# i2-mb_rpi_s.net
KiCad netlist of a schematic drawn in EAGLE
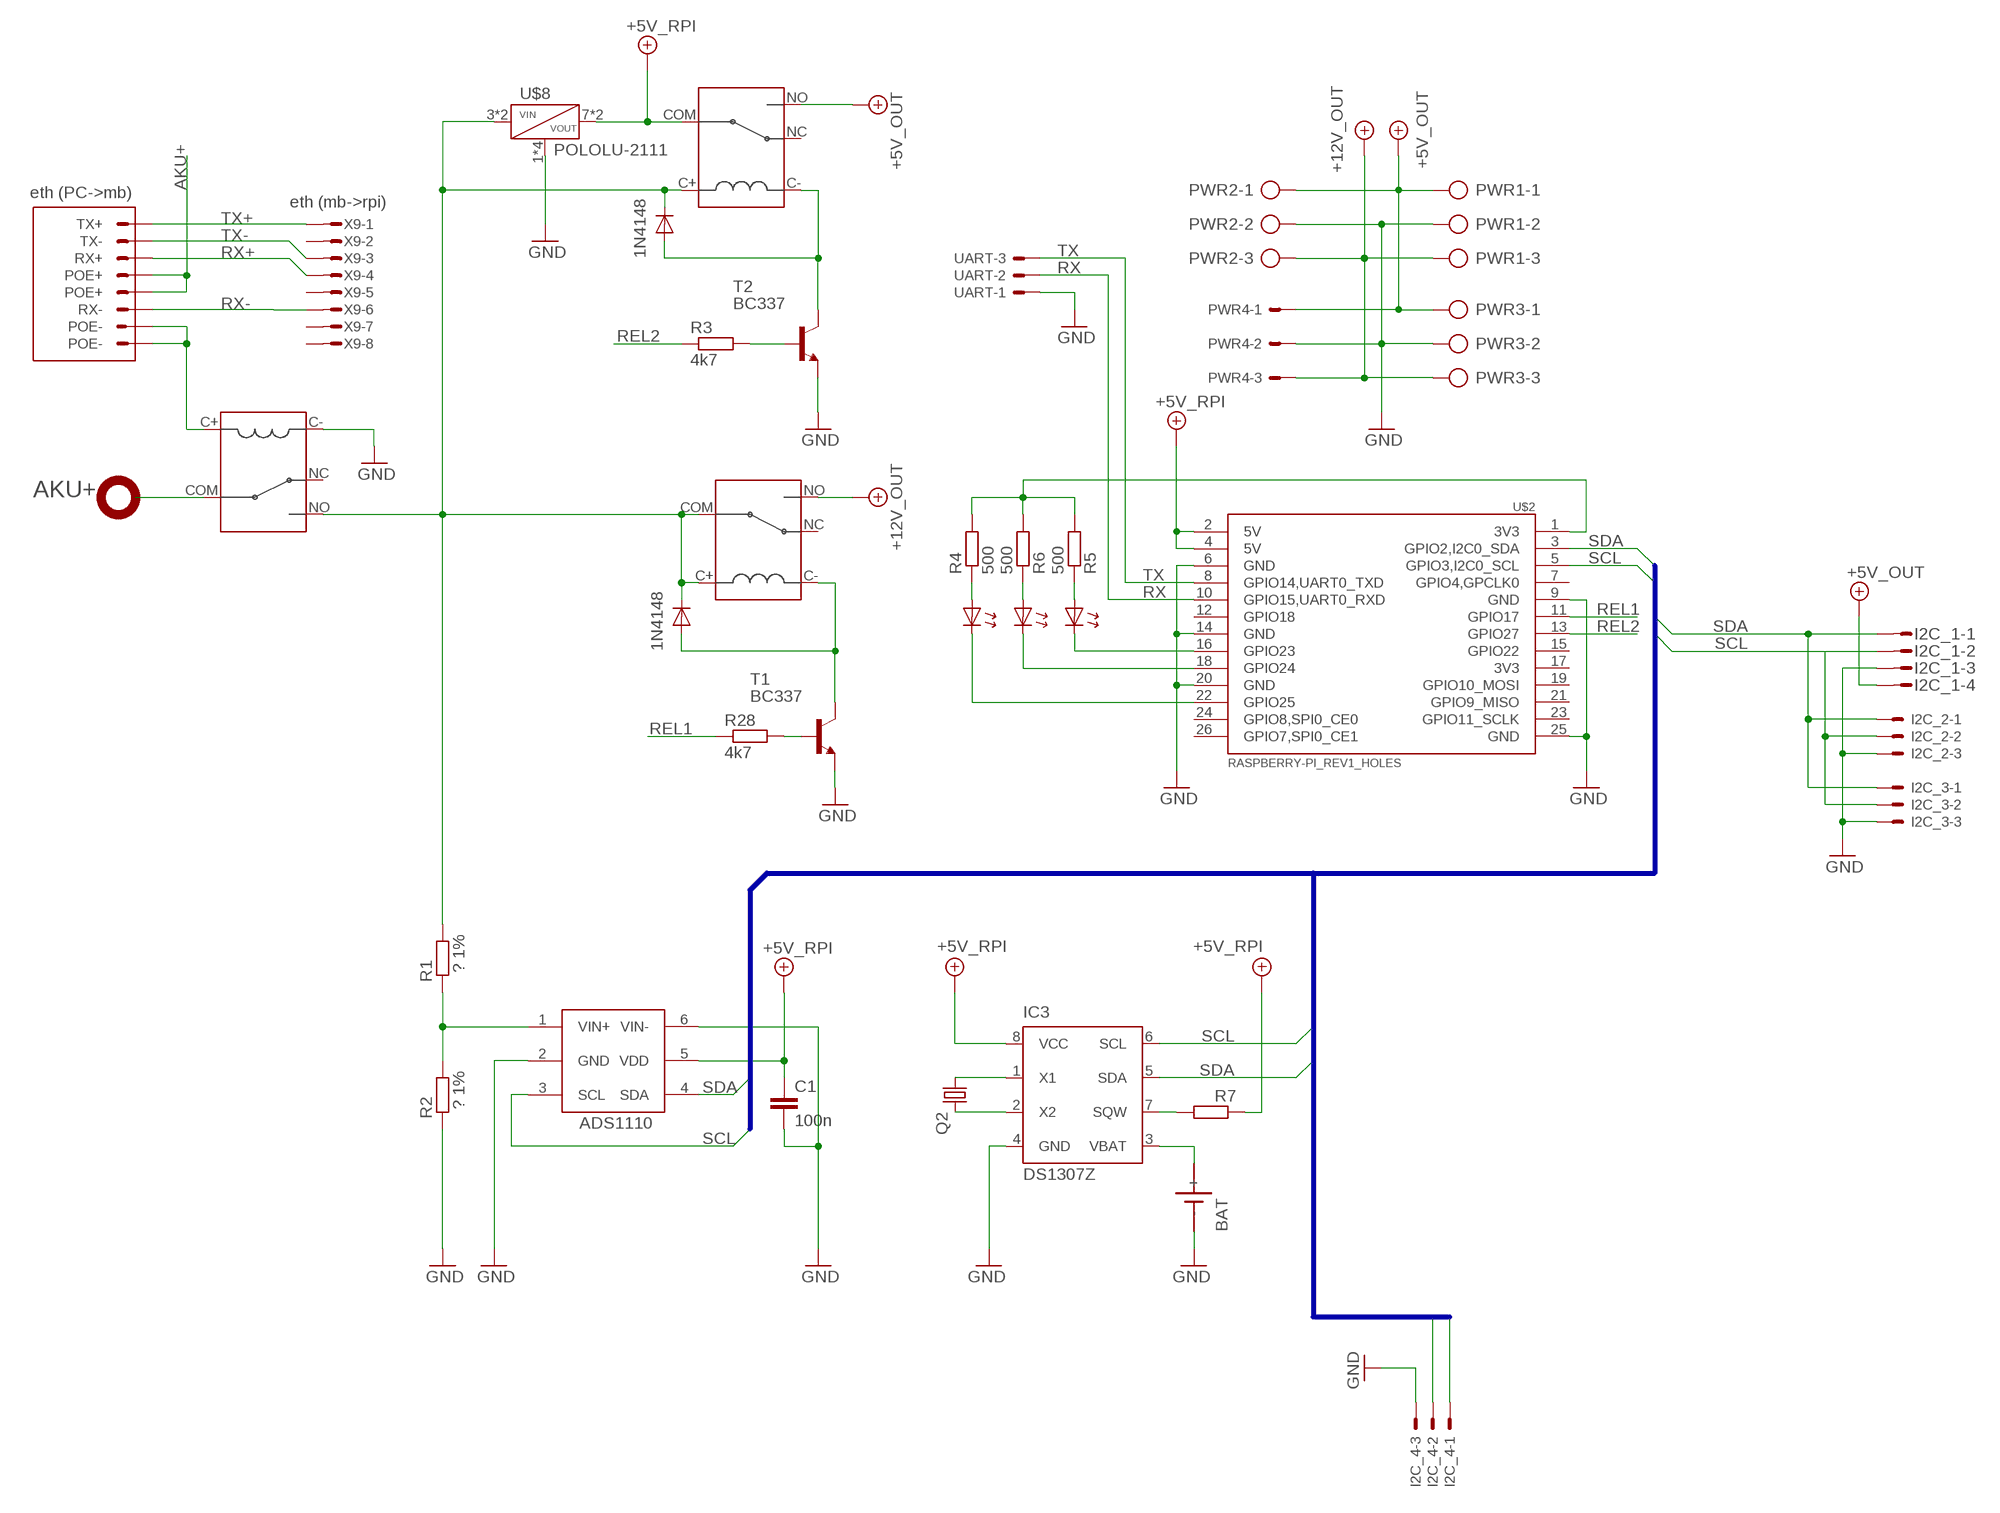
[diagram p0: schematic, sheet 1]

(export (version "E")
  (design (tool "Eeschema 10.0.6"))
  (components
    (comp (ref "BAT")
      (value "SN2032")
      (footprint "eagle-import:SN2032")
      (libsource (lib "eagle-import") (part "SN2032"))
    )
    (comp (ref "C1")
      (value "100n")
      (footprint "eagle-import:C0603")
      (libsource (lib "eagle-import") (part "C-EUC0603"))
    )
    (comp (ref "I2C_1")
      (value "MICROMATCH-4")
      (footprint "eagle-import:MICROMATCH-4")
      (fields (field (name "MPN") "7-215464-4"))
      (libsource (lib "eagle-import") (part "MICROMATCH-4"))
    )
    (comp (ref "I2C_2")
      (value "C-GRID-03-70553")
      (footprint "eagle-import:70553-03")
      (libsource (lib "eagle-import") (part "C-GRID-03-70553"))
    )
    (comp (ref "I2C_3")
      (value "C-GRID-03-70553")
      (footprint "eagle-import:70553-03")
      (libsource (lib "eagle-import") (part "C-GRID-03-70553"))
    )
    (comp (ref "I2C_4")
      (value "C-GRID-03-70553")
      (footprint "eagle-import:70553-03")
      (libsource (lib "eagle-import") (part "C-GRID-03-70553"))
    )
    (comp (ref "IC1")
      (value "ADS1110")
      (footprint "eagle-import:SOT-23-6")
      (libsource (lib "eagle-import") (part "ADS1110"))
    )
    (comp (ref "IC3")
      (value "DS1307Z")
      (footprint "eagle-import:SOIC8")
      (libsource (lib "eagle-import") (part "DS1307Z"))
    )
    (comp (ref "LED1")
      (value "LED0603")
      (footprint "eagle-import:D0603")
      (libsource (lib "eagle-import") (part "LED0603"))
    )
    (comp (ref "LED2")
      (value "LED0603")
      (footprint "eagle-import:D0603")
      (libsource (lib "eagle-import") (part "LED0603"))
    )
    (comp (ref "LED3")
      (value "LED0603")
      (footprint "eagle-import:D0603")
      (libsource (lib "eagle-import") (part "LED0603"))
    )
    (comp (ref "PWR1")
      (value "TBMP5103RC-KFV1")
      (footprint "eagle-import:TBMP5103RC-KF")
      (libsource (lib "eagle-import") (part "TBMP5103RC-KFV1"))
    )
    (comp (ref "PWR2")
      (value "TBMP5103RC-KFV1")
      (footprint "eagle-import:TBMP5103RC-KF")
      (libsource (lib "eagle-import") (part "TBMP5103RC-KFV1"))
    )
    (comp (ref "PWR3")
      (value "TBMP5103RC-KFV1")
      (footprint "eagle-import:TBMP5103RC-KF")
      (libsource (lib "eagle-import") (part "TBMP5103RC-KFV1"))
    )
    (comp (ref "PWR4")
      (value "C-GRID-03-70543")
      (footprint "eagle-import:70543-03")
      (libsource (lib "eagle-import") (part "C-GRID-03-70543"))
    )
    (comp (ref "Q2")
      (value "CRYSTAL")
      (footprint "eagle-import:CFPX-217")
      (libsource (lib "eagle-import") (part "CRYSTAL"))
    )
    (comp (ref "R1")
      (value "? 1%")
      (footprint "eagle-import:R0603")
      (libsource (lib "eagle-import") (part "R-EU_R0603"))
    )
    (comp (ref "R2")
      (value "? 1%")
      (footprint "eagle-import:R0603")
      (libsource (lib "eagle-import") (part "R-EU_R0603"))
    )
    (comp (ref "R3")
      (value "4k7")
      (footprint "eagle-import:R0603")
      (libsource (lib "eagle-import") (part "R-EU_R0603"))
    )
    (comp (ref "R4")
      (value "500")
      (footprint "eagle-import:R0603")
      (libsource (lib "eagle-import") (part "R-EU_R0603"))
    )
    (comp (ref "R5")
      (value "500")
      (footprint "eagle-import:R0603")
      (libsource (lib "eagle-import") (part "R-EU_R0603"))
    )
    (comp (ref "R6")
      (value "500")
      (footprint "eagle-import:R0603")
      (libsource (lib "eagle-import") (part "R-EU_R0603"))
    )
    (comp (ref "R7")
      (value "R-EU_R0603")
      (footprint "eagle-import:R0603")
      (libsource (lib "eagle-import") (part "R-EU_R0603"))
    )
    (comp (ref "R28")
      (value "4k7")
      (footprint "eagle-import:R0603")
      (libsource (lib "eagle-import") (part "R-EU_R0603"))
    )
    (comp (ref "T1")
      (value "BC337")
      (footprint "eagle-import:TO92")
      (libsource (lib "eagle-import") (part "BC337"))
    )
    (comp (ref "T2")
      (value "BC337")
      (footprint "eagle-import:TO92")
      (libsource (lib "eagle-import") (part "BC337"))
    )
    (comp (ref "U$2")
      (value "RASPBERRY-PI_REV1_HOLES")
      (footprint "eagle-import:RASPBERRY-PI_HOLES")
      (libsource (lib "eagle-import") (part "RASPBERRY-PI_REV1_HOLES"))
    )
    (comp (ref "U$3")
      (value "1N4148")
      (footprint "eagle-import:D0603")
      (libsource (lib "eagle-import") (part "D0603"))
    )
    (comp (ref "U$4")
      (value "1N4148")
      (footprint "eagle-import:D0603")
      (libsource (lib "eagle-import") (part "D0603"))
    )
    (comp (ref "U$5")
      (value "FBR51")
      (footprint "eagle-import:PC_RELAY")
      (libsource (lib "eagle-import") (part "FBR51"))
    )
    (comp (ref "U$6")
      (value "FBR51")
      (footprint "eagle-import:PC_RELAY")
      (libsource (lib "eagle-import") (part "FBR51"))
    )
    (comp (ref "U$7")
      (value "FBR51")
      (footprint "eagle-import:PC_RELAY")
      (libsource (lib "eagle-import") (part "FBR51"))
    )
    (comp (ref "U$8")
      (value "POLOLU-2111")
      (footprint "eagle-import:POLOLU-2111")
      (libsource (lib "eagle-import") (part "POLOLU-2111"))
    )
    (comp (ref "UART")
      (value "C-GRID-03-70543")
      (footprint "eagle-import:70543-03")
      (libsource (lib "eagle-import") (part "C-GRID-03-70543"))
    )
    (comp (ref "X9")
      (value "eth (mb->rpi)")
      (footprint "eagle-import:MICROMATCH-8")
      (libsource (lib "eagle-import") (part "MICROMATCH-8"))
    )
    (comp (ref "X_ETH")
      (value "eth (PC->mb)")
      (footprint "eagle-import:8P8C-TOP")
      (libsource (lib "eagle-import") (part "RJ45"))
    )
  )
  (nets
    (net (code "1") (name "+5V_OUT") (class "Default")
      (node (ref "I2C_1") (pin "4") (pinfunction "S_4") (pintype "passive"))
      (node (ref "PWR1") (pin "1") (pinfunction "P_1") (pintype "passive"))
      (node (ref "PWR2") (pin "1") (pinfunction "P_1") (pintype "passive"))
      (node (ref "PWR3") (pin "1") (pinfunction "P_1") (pintype "passive"))
      (node (ref "PWR4") (pin "1") (pinfunction "S_1") (pintype "passive"))
      (node (ref "U$5") (pin "NO") (pinfunction "NO_NO") (pintype "bidirectional"))
    )
    (net (code "2") (name "+5V_RPI") (class "Default")
      (node (ref "C1") (pin "1") (pinfunction "1_1") (pintype "passive"))
      (node (ref "IC1") (pin "5") (pinfunction "VDD_5") (pintype "bidirectional"))
      (node (ref "IC3") (pin "8") (pinfunction "VCC_8") (pintype "power_in"))
      (node (ref "R7") (pin "1") (pinfunction "1_1") (pintype "passive"))
      (node (ref "U$2") (pin "2") (pinfunction "5V_2") (pintype "bidirectional"))
      (node (ref "U$2") (pin "4") (pinfunction "5V_4") (pintype "bidirectional"))
      (node (ref "U$5") (pin "COM") (pinfunction "COM_COM") (pintype "bidirectional"))
      (node (ref "U$8") (pin "7") (pinfunction "VOUT_7") (pintype "passive"))
      (node (ref "U$8") (pin "8") (pinfunction "VOUT_8") (pintype "passive"))
    )
    (net (code "3") (name "+12V_OUT") (class "Default")
      (node (ref "PWR1") (pin "3") (pinfunction "P_3") (pintype "passive"))
      (node (ref "PWR2") (pin "3") (pinfunction "P_3") (pintype "passive"))
      (node (ref "PWR3") (pin "3") (pinfunction "P_3") (pintype "passive"))
      (node (ref "PWR4") (pin "3") (pinfunction "S_3") (pintype "passive"))
      (node (ref "U$7") (pin "NO") (pinfunction "NO_NO") (pintype "bidirectional"))
    )
    (net (code "4") (name "/AKU+") (class "Default")
      (node (ref "U$6") (pin "COM") (pinfunction "COM_COM") (pintype "bidirectional"))
      (node (ref "X_ETH") (pin "4") (pinfunction "POE+_4") (pintype "bidirectional"))
      (node (ref "X_ETH") (pin "5") (pinfunction "POE+_5") (pintype "bidirectional"))
    )
    (net (code "5") (name "/REL1") (class "Default")
      (node (ref "R28") (pin "1") (pinfunction "1_1") (pintype "passive"))
      (node (ref "U$2") (pin "11") (pinfunction "GPIO17_11") (pintype "bidirectional"))
    )
    (net (code "6") (name "/REL2") (class "Default")
      (node (ref "R3") (pin "1") (pinfunction "1_1") (pintype "passive"))
      (node (ref "U$2") (pin "13") (pinfunction "GPIO27_13") (pintype "bidirectional"))
    )
    (net (code "7") (name "/RX") (class "Default")
      (node (ref "U$2") (pin "10") (pinfunction "GPIO15,UART0_RXD_10") (pintype "bidirectional"))
      (node (ref "UART") (pin "2") (pinfunction "S_2") (pintype "passive"))
    )
    (net (code "8") (name "/RX+") (class "Default")
      (node (ref "X9") (pin "4") (pinfunction "S_4") (pintype "passive"))
      (node (ref "X_ETH") (pin "3") (pinfunction "RX+_3") (pintype "bidirectional"))
    )
    (net (code "9") (name "/RX-") (class "Default")
      (node (ref "X9") (pin "6") (pinfunction "S_6") (pintype "passive"))
      (node (ref "X_ETH") (pin "6") (pinfunction "RX-_6") (pintype "bidirectional"))
    )
    (net (code "10") (name "/SCL") (class "Default")
      (node (ref "I2C_1") (pin "2") (pinfunction "S_2") (pintype "passive"))
      (node (ref "I2C_2") (pin "2") (pinfunction "S_2") (pintype "passive"))
      (node (ref "I2C_3") (pin "2") (pinfunction "S_2") (pintype "passive"))
      (node (ref "I2C_4") (pin "2") (pinfunction "S_2") (pintype "passive"))
      (node (ref "IC1") (pin "3") (pinfunction "SCL_3") (pintype "bidirectional"))
      (node (ref "IC3") (pin "6") (pinfunction "SCL_6") (pintype "input"))
      (node (ref "U$2") (pin "5") (pinfunction "GPIO3,I2C0_SCL_5") (pintype "bidirectional"))
    )
    (net (code "11") (name "/SDA") (class "Default")
      (node (ref "I2C_1") (pin "1") (pinfunction "S_1") (pintype "passive"))
      (node (ref "I2C_2") (pin "1") (pinfunction "S_1") (pintype "passive"))
      (node (ref "I2C_3") (pin "1") (pinfunction "S_1") (pintype "passive"))
      (node (ref "I2C_4") (pin "1") (pinfunction "S_1") (pintype "passive"))
      (node (ref "IC1") (pin "4") (pinfunction "SDA_4") (pintype "bidirectional"))
      (node (ref "IC3") (pin "5") (pinfunction "SDA_5") (pintype "bidirectional"))
      (node (ref "U$2") (pin "3") (pinfunction "GPIO2,I2C0_SDA_3") (pintype "bidirectional"))
    )
    (net (code "12") (name "/TX") (class "Default")
      (node (ref "U$2") (pin "8") (pinfunction "GPIO14,UART0_TXD_8") (pintype "bidirectional"))
      (node (ref "UART") (pin "3") (pinfunction "S_3") (pintype "passive"))
    )
    (net (code "13") (name "/TX+") (class "Default")
      (node (ref "X9") (pin "1") (pinfunction "S_1") (pintype "passive"))
      (node (ref "X_ETH") (pin "1") (pinfunction "TX+_1") (pintype "bidirectional"))
    )
    (net (code "14") (name "/TX-") (class "Default")
      (node (ref "X9") (pin "3") (pinfunction "S_3") (pintype "passive"))
      (node (ref "X_ETH") (pin "2") (pinfunction "TX-_2") (pintype "bidirectional"))
    )
    (net (code "15") (name "GND") (class "Default")
      (node (ref "BAT") (pin "-") (pinfunction "-_-") (pintype "passive"))
      (node (ref "C1") (pin "2") (pinfunction "2_2") (pintype "passive"))
      (node (ref "I2C_1") (pin "3") (pinfunction "S_3") (pintype "passive"))
      (node (ref "I2C_2") (pin "3") (pinfunction "S_3") (pintype "passive"))
      (node (ref "I2C_3") (pin "3") (pinfunction "S_3") (pintype "passive"))
      (node (ref "I2C_4") (pin "3") (pinfunction "S_3") (pintype "passive"))
      (node (ref "IC1") (pin "2") (pinfunction "GND_2") (pintype "bidirectional"))
      (node (ref "IC1") (pin "6") (pinfunction "VIN-_6") (pintype "bidirectional"))
      (node (ref "IC3") (pin "4") (pinfunction "GND_4") (pintype "power_in"))
      (node (ref "PWR1") (pin "2") (pinfunction "P_2") (pintype "passive"))
      (node (ref "PWR2") (pin "2") (pinfunction "P_2") (pintype "passive"))
      (node (ref "PWR3") (pin "2") (pinfunction "P_2") (pintype "passive"))
      (node (ref "PWR4") (pin "2") (pinfunction "S_2") (pintype "passive"))
      (node (ref "R2") (pin "2") (pinfunction "2_2") (pintype "passive"))
      (node (ref "T1") (pin "1") (pinfunction "E_1") (pintype "passive"))
      (node (ref "T2") (pin "1") (pinfunction "E_1") (pintype "passive"))
      (node (ref "U$2") (pin "14") (pinfunction "GND_14") (pintype "bidirectional"))
      (node (ref "U$2") (pin "20") (pinfunction "GND_20") (pintype "bidirectional"))
      (node (ref "U$2") (pin "25") (pinfunction "GND_25") (pintype "bidirectional"))
      (node (ref "U$2") (pin "6") (pinfunction "GND_6") (pintype "bidirectional"))
      (node (ref "U$2") (pin "9") (pinfunction "GND_9") (pintype "bidirectional"))
      (node (ref "U$6") (pin "C-") (pinfunction "C-_C-") (pintype "bidirectional"))
      (node (ref "U$8") (pin "1") (pinfunction "GND_1") (pintype "passive"))
      (node (ref "U$8") (pin "2") (pinfunction "GND_2") (pintype "passive"))
      (node (ref "U$8") (pin "5") (pinfunction "GND_5") (pintype "passive"))
      (node (ref "U$8") (pin "6") (pinfunction "GND_6") (pintype "passive"))
      (node (ref "UART") (pin "1") (pinfunction "S_1") (pintype "passive"))
    )
    (net (code "16") (name "Net-(IC1-VIN+)") (class "Default")
      (node (ref "IC1") (pin "1") (pinfunction "VIN+_1") (pintype "bidirectional"))
      (node (ref "R1") (pin "2") (pinfunction "2_2") (pintype "passive"))
      (node (ref "R2") (pin "1") (pinfunction "1_1") (pintype "passive"))
    )
    (net (code "17") (name "Net-(IC3-SQW)") (class "Default")
      (node (ref "IC3") (pin "7") (pinfunction "SQW_7") (pintype "open_collector"))
      (node (ref "R7") (pin "2") (pinfunction "2_2") (pintype "passive"))
    )
    (net (code "18") (name "Net-(IC3-VBAT)") (class "Default")
      (node (ref "BAT") (pin "+") (pinfunction "+_+") (pintype "passive"))
      (node (ref "IC3") (pin "3") (pinfunction "VBAT_3") (pintype "passive"))
    )
    (net (code "19") (name "Net-(IC3-X1)") (class "Default")
      (node (ref "IC3") (pin "1") (pinfunction "X1_1") (pintype "input"))
      (node (ref "Q2") (pin "1") (pinfunction "1_1") (pintype "passive"))
    )
    (net (code "20") (name "Net-(IC3-X2)") (class "Default")
      (node (ref "IC3") (pin "2") (pinfunction "X2_2") (pintype "output"))
      (node (ref "Q2") (pin "2") (pinfunction "2_2") (pintype "passive"))
    )
    (net (code "21") (name "Net-(LED1-A)") (class "Default")
      (node (ref "LED1") (pin "1") (pinfunction "A_1") (pintype "passive"))
      (node (ref "R4") (pin "1") (pinfunction "1_1") (pintype "passive"))
    )
    (net (code "22") (name "Net-(LED1-C)") (class "Default")
      (node (ref "LED1") (pin "2") (pinfunction "C_2") (pintype "passive"))
      (node (ref "U$2") (pin "22") (pinfunction "GPIO25_22") (pintype "bidirectional"))
    )
    (net (code "23") (name "Net-(LED2-A)") (class "Default")
      (node (ref "LED2") (pin "1") (pinfunction "A_1") (pintype "passive"))
      (node (ref "R5") (pin "1") (pinfunction "1_1") (pintype "passive"))
    )
    (net (code "24") (name "Net-(LED2-C)") (class "Default")
      (node (ref "LED2") (pin "2") (pinfunction "C_2") (pintype "passive"))
      (node (ref "U$2") (pin "16") (pinfunction "GPIO23_16") (pintype "bidirectional"))
    )
    (net (code "25") (name "Net-(LED3-A)") (class "Default")
      (node (ref "LED3") (pin "1") (pinfunction "A_1") (pintype "passive"))
      (node (ref "R6") (pin "1") (pinfunction "1_1") (pintype "passive"))
    )
    (net (code "26") (name "Net-(LED3-C)") (class "Default")
      (node (ref "LED3") (pin "2") (pinfunction "C_2") (pintype "passive"))
      (node (ref "U$2") (pin "18") (pinfunction "GPIO24_18") (pintype "bidirectional"))
    )
    (net (code "27") (name "Net-(R4-Pad2)") (class "Default")
      (node (ref "R4") (pin "2") (pinfunction "2_2") (pintype "passive"))
      (node (ref "R5") (pin "2") (pinfunction "2_2") (pintype "passive"))
      (node (ref "R6") (pin "2") (pinfunction "2_2") (pintype "passive"))
      (node (ref "U$2") (pin "1") (pinfunction "3V3_1") (pintype "bidirectional"))
    )
    (net (code "28") (name "Net-(T1-B)") (class "Default")
      (node (ref "R28") (pin "2") (pinfunction "2_2") (pintype "passive"))
      (node (ref "T1") (pin "2") (pinfunction "B_2") (pintype "passive"))
    )
    (net (code "29") (name "Net-(T1-C)") (class "Default")
      (node (ref "T1") (pin "3") (pinfunction "C_3") (pintype "passive"))
      (node (ref "U$4") (pin "1") (pinfunction "A_1") (pintype "passive"))
      (node (ref "U$7") (pin "C-") (pinfunction "C-_C-") (pintype "bidirectional"))
    )
    (net (code "30") (name "Net-(T2-B)") (class "Default")
      (node (ref "R3") (pin "2") (pinfunction "2_2") (pintype "passive"))
      (node (ref "T2") (pin "2") (pinfunction "B_2") (pintype "passive"))
    )
    (net (code "31") (name "Net-(T2-C)") (class "Default")
      (node (ref "T2") (pin "3") (pinfunction "C_3") (pintype "passive"))
      (node (ref "U$3") (pin "1") (pinfunction "A_1") (pintype "passive"))
      (node (ref "U$5") (pin "C-") (pinfunction "C-_C-") (pintype "bidirectional"))
    )
    (net (code "32") (name "Net-(U$3-C)") (class "Default")
      (node (ref "R1") (pin "1") (pinfunction "1_1") (pintype "passive"))
      (node (ref "U$3") (pin "2") (pinfunction "C_2") (pintype "passive"))
      (node (ref "U$4") (pin "2") (pinfunction "C_2") (pintype "passive"))
      (node (ref "U$5") (pin "C+") (pinfunction "C+_C+") (pintype "bidirectional"))
      (node (ref "U$6") (pin "NO") (pinfunction "NO_NO") (pintype "bidirectional"))
      (node (ref "U$7") (pin "C+") (pinfunction "C+_C+") (pintype "bidirectional"))
      (node (ref "U$7") (pin "COM") (pinfunction "COM_COM") (pintype "bidirectional"))
      (node (ref "U$8") (pin "3") (pinfunction "VIN_3") (pintype "passive"))
      (node (ref "U$8") (pin "4") (pinfunction "VIN_4") (pintype "passive"))
    )
    (net (code "33") (name "Net-(U$6-PadC+)") (class "Default")
      (node (ref "U$6") (pin "C+") (pinfunction "C+_C+") (pintype "bidirectional"))
      (node (ref "X_ETH") (pin "7") (pinfunction "POE-_7") (pintype "bidirectional"))
      (node (ref "X_ETH") (pin "8") (pinfunction "POE-_8") (pintype "bidirectional"))
    )
    (net (code "34") (name "unconnected-(U$2-3V3-Pad17)") (class "Default")
      (node (ref "U$2") (pin "17") (pinfunction "3V3_17") (pintype "bidirectional"))
    )
    (net (code "35") (name "unconnected-(U$2-GPIO4,GPCLK0-Pad7)") (class "Default")
      (node (ref "U$2") (pin "7") (pinfunction "GPIO4,GPCLK0_7") (pintype "bidirectional"))
    )
    (net (code "36") (name "unconnected-(U$2-GPIO7,SPI0_CE1-Pad26)") (class "Default")
      (node (ref "U$2") (pin "26") (pinfunction "GPIO7,SPI0_CE1_26") (pintype "bidirectional"))
    )
    (net (code "37") (name "unconnected-(U$2-GPIO8,SPI0_CE0-Pad24)") (class "Default")
      (node (ref "U$2") (pin "24") (pinfunction "GPIO8,SPI0_CE0_24") (pintype "bidirectional"))
    )
    (net (code "38") (name "unconnected-(U$2-GPIO9_MISO-Pad21)") (class "Default")
      (node (ref "U$2") (pin "21") (pinfunction "GPIO9_MISO_21") (pintype "bidirectional"))
    )
    (net (code "39") (name "unconnected-(U$2-GPIO10_MOSI-Pad19)") (class "Default")
      (node (ref "U$2") (pin "19") (pinfunction "GPIO10_MOSI_19") (pintype "bidirectional"))
    )
    (net (code "40") (name "unconnected-(U$2-GPIO11_SCLK-Pad23)") (class "Default")
      (node (ref "U$2") (pin "23") (pinfunction "GPIO11_SCLK_23") (pintype "bidirectional"))
    )
    (net (code "41") (name "unconnected-(U$2-GPIO18-Pad12)") (class "Default")
      (node (ref "U$2") (pin "12") (pinfunction "GPIO18_12") (pintype "bidirectional"))
    )
    (net (code "42") (name "unconnected-(U$2-GPIO22-Pad15)") (class "Default")
      (node (ref "U$2") (pin "15") (pinfunction "GPIO22_15") (pintype "bidirectional"))
    )
    (net (code "43") (name "unconnected-(U$5-PadNC)") (class "Default")
      (node (ref "U$5") (pin "NC") (pinfunction "NC_NC") (pintype "bidirectional"))
    )
    (net (code "44") (name "unconnected-(U$6-PadNC)") (class "Default")
      (node (ref "U$6") (pin "NC") (pinfunction "NC_NC") (pintype "bidirectional"))
    )
    (net (code "45") (name "unconnected-(U$7-PadNC)") (class "Default")
      (node (ref "U$7") (pin "NC") (pinfunction "NC_NC") (pintype "bidirectional"))
    )
    (net (code "46") (name "unconnected-(X9B-S-Pad2)") (class "Default")
      (node (ref "X9") (pin "2") (pinfunction "S_2") (pintype "passive"))
    )
    (net (code "47") (name "unconnected-(X9E-S-Pad5)") (class "Default")
      (node (ref "X9") (pin "5") (pinfunction "S_5") (pintype "passive"))
    )
    (net (code "48") (name "unconnected-(X9G-S-Pad7)") (class "Default")
      (node (ref "X9") (pin "7") (pinfunction "S_7") (pintype "passive"))
    )
    (net (code "49") (name "unconnected-(X9H-S-Pad8)") (class "Default")
      (node (ref "X9") (pin "8") (pinfunction "S_8") (pintype "passive"))
    )
  )
)
